# SchematicV0.net
KiCad netlist of a schematic drawn in Altium Designer
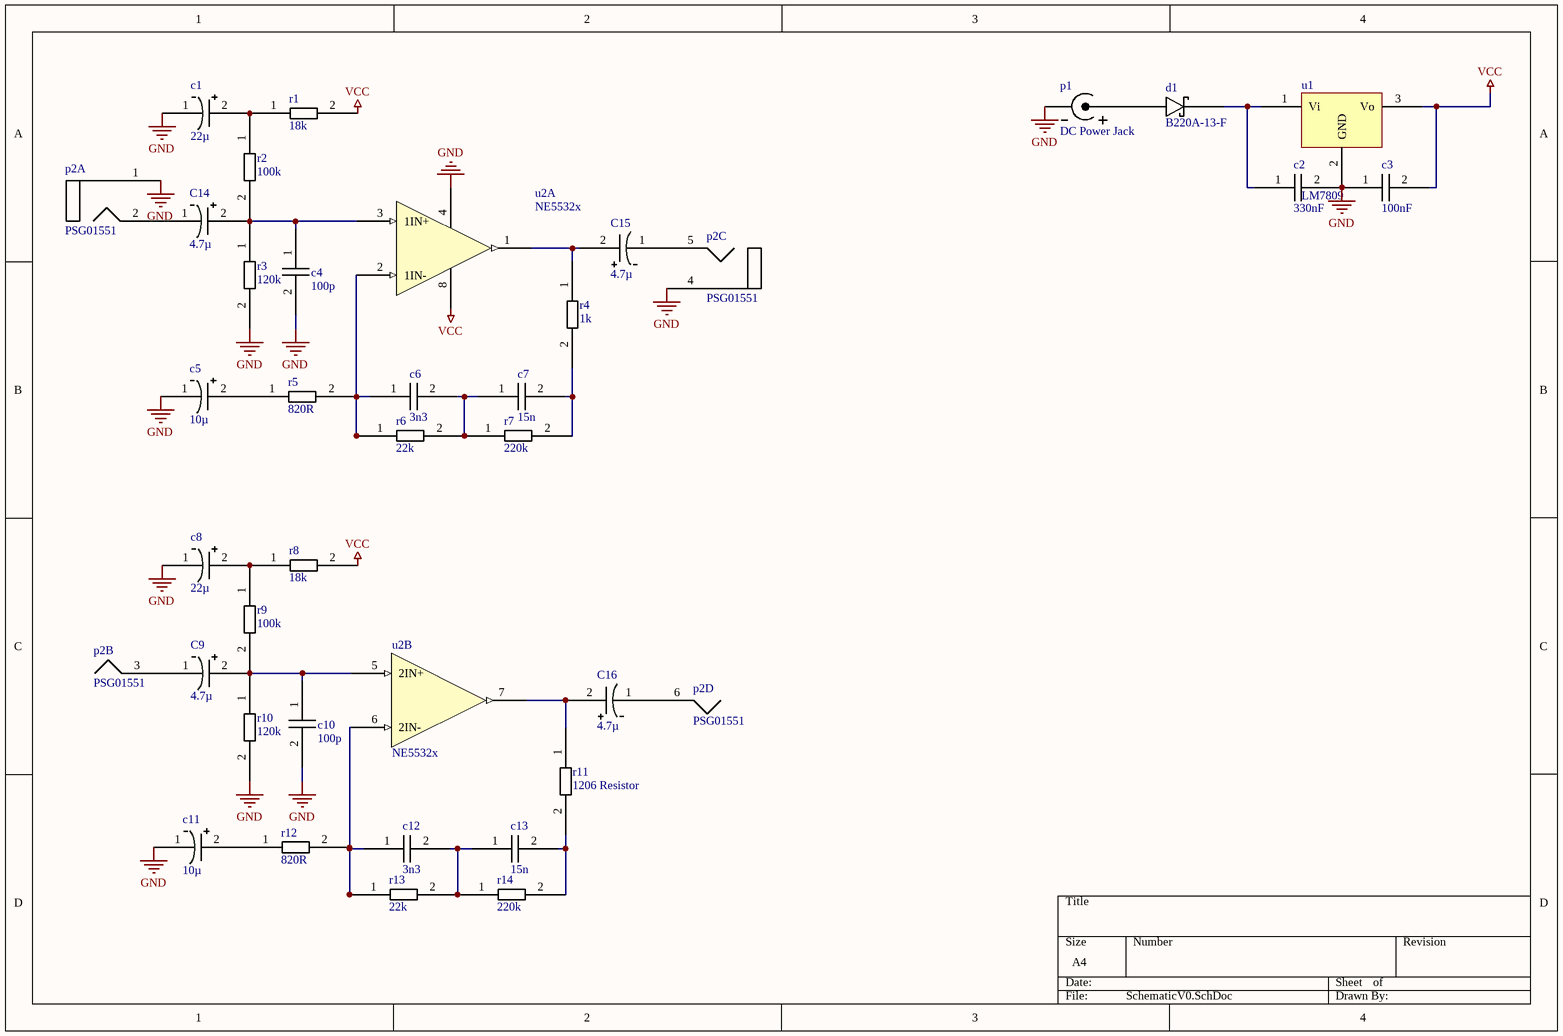
[diagram p0: SchematicV0.SchDoc]

(export (version "E")
  (design (tool "Eeschema 10.0.6"))
  (components
    (comp (ref "c1")
      (value "22µ")
      (footprint "Elco-D")
      (description "Elco size D 6.3x5.4")
      (libsource (lib "Panasonic") (part "Elco D"))
    )
    (comp (ref "c2")
      (value "330nF")
      (footprint "1206")
      (description "Capacitor package 1206")
      (libsource (lib "Generic R-C") (part "1206 100pF"))
    )
    (comp (ref "c3")
      (value "100nF")
      (footprint "1206")
      (description "Capacitor package 1206")
      (libsource (lib "Generic R-C") (part "1206 100pF"))
    )
    (comp (ref "c4")
      (value "100p")
      (footprint "1206")
      (description "Capacitor package 1206")
      (libsource (lib "Generic R-C") (part "1206 Cap"))
    )
    (comp (ref "c5") (value "10µ") (footprint "Elco-C") (libsource (lib "Panasonic") (part "Elco C")))
    (comp (ref "c6")
      (value "3n3")
      (footprint "1206")
      (description "Capacitor package 1206")
      (libsource (lib "Generic R-C") (part "1206 Cap"))
    )
    (comp (ref "c7")
      (value "15n")
      (footprint "1206")
      (description "Capacitor package 1206")
      (libsource (lib "Generic R-C") (part "1206 Cap"))
    )
    (comp (ref "c8")
      (value "22µ")
      (footprint "Elco-D")
      (description "Elco size D 6.3x5.4")
      (libsource (lib "Panasonic") (part "Elco D"))
    )
    (comp (ref "C9") (value "4.7µ") (footprint "Elco-C") (libsource (lib "Panasonic") (part "Elco C")))
    (comp (ref "c10")
      (value "100p")
      (footprint "1206")
      (description "Capacitor package 1206")
      (libsource (lib "Generic R-C") (part "1206 Cap"))
    )
    (comp (ref "c11") (value "10µ") (footprint "Elco-C") (libsource (lib "Panasonic") (part "Elco C")))
    (comp (ref "c12")
      (value "3n3")
      (footprint "1206")
      (description "Capacitor package 1206")
      (libsource (lib "Generic R-C") (part "1206 Cap"))
    )
    (comp (ref "c13")
      (value "15n")
      (footprint "1206")
      (description "Capacitor package 1206")
      (libsource (lib "Generic R-C") (part "1206 Cap"))
    )
    (comp (ref "C14") (value "4.7µ") (footprint "Elco-C") (libsource (lib "Panasonic") (part "Elco C")))
    (comp (ref "C15") (value "4.7µ") (footprint "Elco-C") (libsource (lib "Panasonic") (part "Elco C")))
    (comp (ref "C16") (value "4.7µ") (footprint "Elco-C") (libsource (lib "Panasonic") (part "Elco C")))
    (comp (ref "d1")
      (value "B220A-13-F")
      (footprint "SMA")
      (description "Schottky Rectifier")
      (libsource (lib "Diodes_inc") (part "B220A-13-F"))
    )
    (comp (ref "p1")
      (value "DC Power Jack")
      (footprint "Power Jack")
      (libsource (lib "Multicomp") (part "DC Power Jack"))
    )
    (comp (ref "p2")
      (value "PSG01551")
      (footprint "RCA 4-way")
      (description "4-way RCA connector")
      (libsource (lib "Pro-Signal") (part "PSG01551"))
    )
    (comp (ref "r1")
      (value "18k")
      (footprint "1206")
      (description "Resistor Package 1206")
      (libsource (lib "Generic R-C") (part "1206 Resistor"))
    )
    (comp (ref "r2")
      (value "100k")
      (footprint "1206")
      (description "Resistor Package 1206")
      (libsource (lib "Generic R-C") (part "1206 Resistor"))
    )
    (comp (ref "r3")
      (value "120k")
      (footprint "1206")
      (description "Resistor Package 1206")
      (libsource (lib "Generic R-C") (part "1206 Resistor"))
    )
    (comp (ref "r4")
      (value "1k")
      (footprint "1206")
      (description "Resistor Package 1206")
      (libsource (lib "Generic R-C") (part "1206 Resistor"))
    )
    (comp (ref "r5")
      (value "820R")
      (footprint "1206")
      (description "Resistor Package 1206")
      (libsource (lib "Generic R-C") (part "1206 Resistor"))
    )
    (comp (ref "r6")
      (value "22k")
      (footprint "1206")
      (description "Resistor Package 1206")
      (libsource (lib "Generic R-C") (part "1206 Resistor"))
    )
    (comp (ref "r7")
      (value "220k")
      (footprint "1206")
      (description "Resistor Package 1206")
      (libsource (lib "Generic R-C") (part "1206 Resistor"))
    )
    (comp (ref "r8")
      (value "18k")
      (footprint "1206")
      (description "Resistor Package 1206")
      (libsource (lib "Generic R-C") (part "1206 Resistor"))
    )
    (comp (ref "r9")
      (value "100k")
      (footprint "1206")
      (description "Resistor Package 1206")
      (libsource (lib "Generic R-C") (part "1206 Resistor"))
    )
    (comp (ref "r10")
      (value "120k")
      (footprint "1206")
      (description "Resistor Package 1206")
      (libsource (lib "Generic R-C") (part "1206 Resistor"))
    )
    (comp (ref "r11")
      (value "1206 Resistor")
      (footprint "1206")
      (description "Resistor Package 1206")
      (libsource (lib "Generic R-C") (part "1206 Resistor"))
    )
    (comp (ref "r12")
      (value "820R")
      (footprint "1206")
      (description "Resistor Package 1206")
      (libsource (lib "Generic R-C") (part "1206 Resistor"))
    )
    (comp (ref "r13")
      (value "22k")
      (footprint "1206")
      (description "Resistor Package 1206")
      (libsource (lib "Generic R-C") (part "1206 Resistor"))
    )
    (comp (ref "r14")
      (value "220k")
      (footprint "1206")
      (description "Resistor Package 1206")
      (libsource (lib "Generic R-C") (part "1206 Resistor"))
    )
    (comp (ref "u1")
      (value "LM7809")
      (footprint "TO-220AB-3")
      (description "Positive voltage regulator to 9V")
      (libsource (lib "Fairchild") (part "LM7809"))
    )
    (comp (ref "u2")
      (value "NE5532x")
      (footprint "R-PDSO-G8-P127d620x530")
      (description "Dual Low-Noise OpAmp")
      (libsource (lib "Texas Instruments") (part "NE5532x"))
    )
  )
  (nets
    (net (code "1") (name "GND") (class "Default")
      (node (ref "c1") (pin "1") (pintype "passive"))
      (node (ref "c10") (pin "2") (pintype "passive"))
      (node (ref "c11") (pin "1") (pintype "passive"))
      (node (ref "c2") (pin "2") (pintype "passive"))
      (node (ref "c3") (pin "1") (pintype "passive"))
      (node (ref "c4") (pin "2") (pintype "passive"))
      (node (ref "c5") (pin "1") (pintype "passive"))
      (node (ref "c8") (pin "1") (pintype "passive"))
      (node (ref "p1") (pin "2") (pinfunction "GND_2") (pintype "power_in"))
      (node (ref "p2") (pin "1") (pintype "power_in"))
      (node (ref "p2") (pin "4") (pintype "power_in"))
      (node (ref "r10") (pin "2") (pintype "passive"))
      (node (ref "r3") (pin "2") (pintype "passive"))
      (node (ref "u1") (pin "2") (pinfunction "GND_2") (pintype "power_in"))
      (node (ref "u2") (pin "4") (pinfunction "Vcc-_4") (pintype "power_in"))
    )
    (net (code "2") (name "Net-(C9-Pad1)") (class "Default")
      (node (ref "C9") (pin "1") (pintype "passive"))
      (node (ref "p2") (pin "3") (pintype "passive"))
    )
    (net (code "3") (name "Net-(C14-Pad1)") (class "Default")
      (node (ref "C14") (pin "1") (pintype "passive"))
      (node (ref "p2") (pin "2") (pintype "passive"))
    )
    (net (code "4") (name "Net-(C15-Pad1)") (class "Default")
      (node (ref "C15") (pin "1") (pintype "passive"))
      (node (ref "p2") (pin "5") (pintype "passive"))
    )
    (net (code "5") (name "Net-(C16-Pad1)") (class "Default")
      (node (ref "C16") (pin "1") (pintype "passive"))
      (node (ref "p2") (pin "6") (pintype "passive"))
    )
    (net (code "6") (name "Net-(c1-Pad2)") (class "Default")
      (node (ref "c1") (pin "2") (pintype "passive"))
      (node (ref "r1") (pin "1") (pintype "passive"))
      (node (ref "r2") (pin "1") (pintype "passive"))
    )
    (net (code "7") (name "Net-(c5-Pad2)") (class "Default")
      (node (ref "c5") (pin "2") (pintype "passive"))
      (node (ref "r5") (pin "1") (pintype "passive"))
    )
    (net (code "8") (name "Net-(c6-Pad2)") (class "Default")
      (node (ref "c6") (pin "2") (pintype "passive"))
      (node (ref "c7") (pin "1") (pintype "passive"))
      (node (ref "r6") (pin "2") (pintype "passive"))
      (node (ref "r7") (pin "1") (pintype "passive"))
    )
    (net (code "9") (name "Net-(c7-Pad2)") (class "Default")
      (node (ref "c7") (pin "2") (pintype "passive"))
      (node (ref "r4") (pin "2") (pintype "passive"))
      (node (ref "r7") (pin "2") (pintype "passive"))
    )
    (net (code "10") (name "Net-(c8-Pad2)") (class "Default")
      (node (ref "c8") (pin "2") (pintype "passive"))
      (node (ref "r8") (pin "1") (pintype "passive"))
      (node (ref "r9") (pin "1") (pintype "passive"))
    )
    (net (code "11") (name "Net-(c11-Pad2)") (class "Default")
      (node (ref "c11") (pin "2") (pintype "passive"))
      (node (ref "r12") (pin "1") (pintype "passive"))
    )
    (net (code "12") (name "Net-(c12-Pad2)") (class "Default")
      (node (ref "c12") (pin "2") (pintype "passive"))
      (node (ref "c13") (pin "1") (pintype "passive"))
      (node (ref "r13") (pin "2") (pintype "passive"))
      (node (ref "r14") (pin "1") (pintype "passive"))
    )
    (net (code "13") (name "Net-(c13-Pad2)") (class "Default")
      (node (ref "c13") (pin "2") (pintype "passive"))
      (node (ref "r11") (pin "2") (pintype "passive"))
      (node (ref "r14") (pin "2") (pintype "passive"))
    )
    (net (code "14") (name "Net-(d1-Anode)") (class "Default")
      (node (ref "d1") (pin "1") (pinfunction "Anode_1") (pintype "passive"))
      (node (ref "p1") (pin "1") (pinfunction "V+_1") (pintype "power_in"))
    )
    (net (code "15") (name "Net-(d1-Kathode)") (class "Default")
      (node (ref "c2") (pin "1") (pintype "passive"))
      (node (ref "d1") (pin "2") (pinfunction "Kathode_2") (pintype "passive"))
      (node (ref "u1") (pin "1") (pinfunction "Vi_1") (pintype "power_in"))
    )
    (net (code "16") (name "Net-(u2A-1IN+)") (class "Default")
      (node (ref "C14") (pin "2") (pintype "passive"))
      (node (ref "c4") (pin "1") (pintype "passive"))
      (node (ref "r2") (pin "2") (pintype "passive"))
      (node (ref "r3") (pin "1") (pintype "passive"))
      (node (ref "u2") (pin "3") (pinfunction "1IN+_3") (pintype "input"))
    )
    (net (code "17") (name "Net-(u2A-1IN-)") (class "Default")
      (node (ref "c6") (pin "1") (pintype "passive"))
      (node (ref "r5") (pin "2") (pintype "passive"))
      (node (ref "r6") (pin "1") (pintype "passive"))
      (node (ref "u2") (pin "2") (pinfunction "1IN-_2") (pintype "input"))
    )
    (net (code "18") (name "Net-(u2A-1OUT)") (class "Default")
      (node (ref "C15") (pin "2") (pintype "passive"))
      (node (ref "r4") (pin "1") (pintype "passive"))
      (node (ref "u2") (pin "1") (pinfunction "1OUT_1") (pintype "output"))
    )
    (net (code "19") (name "Net-(u2B-2IN+)") (class "Default")
      (node (ref "C9") (pin "2") (pintype "passive"))
      (node (ref "c10") (pin "1") (pintype "passive"))
      (node (ref "r10") (pin "1") (pintype "passive"))
      (node (ref "r9") (pin "2") (pintype "passive"))
      (node (ref "u2") (pin "5") (pinfunction "2IN+_5") (pintype "input"))
    )
    (net (code "20") (name "Net-(u2B-2IN-)") (class "Default")
      (node (ref "c12") (pin "1") (pintype "passive"))
      (node (ref "r12") (pin "2") (pintype "passive"))
      (node (ref "r13") (pin "1") (pintype "passive"))
      (node (ref "u2") (pin "6") (pinfunction "2IN-_6") (pintype "input"))
    )
    (net (code "21") (name "Net-(u2B-2OUT)") (class "Default")
      (node (ref "C16") (pin "2") (pintype "passive"))
      (node (ref "r11") (pin "1") (pintype "passive"))
      (node (ref "u2") (pin "7") (pinfunction "2OUT_7") (pintype "output"))
    )
    (net (code "22") (name "VCC") (class "Default")
      (node (ref "c3") (pin "2") (pintype "passive"))
      (node (ref "r1") (pin "2") (pintype "passive"))
      (node (ref "r8") (pin "2") (pintype "passive"))
      (node (ref "u1") (pin "3") (pinfunction "Vo_3") (pintype "power_in"))
      (node (ref "u2") (pin "8") (pinfunction "Vcc+_8") (pintype "power_in"))
    )
  )
)
